# nrf52-coprocessor.net
KiCad netlist of a schematic drawn in Altium Designer
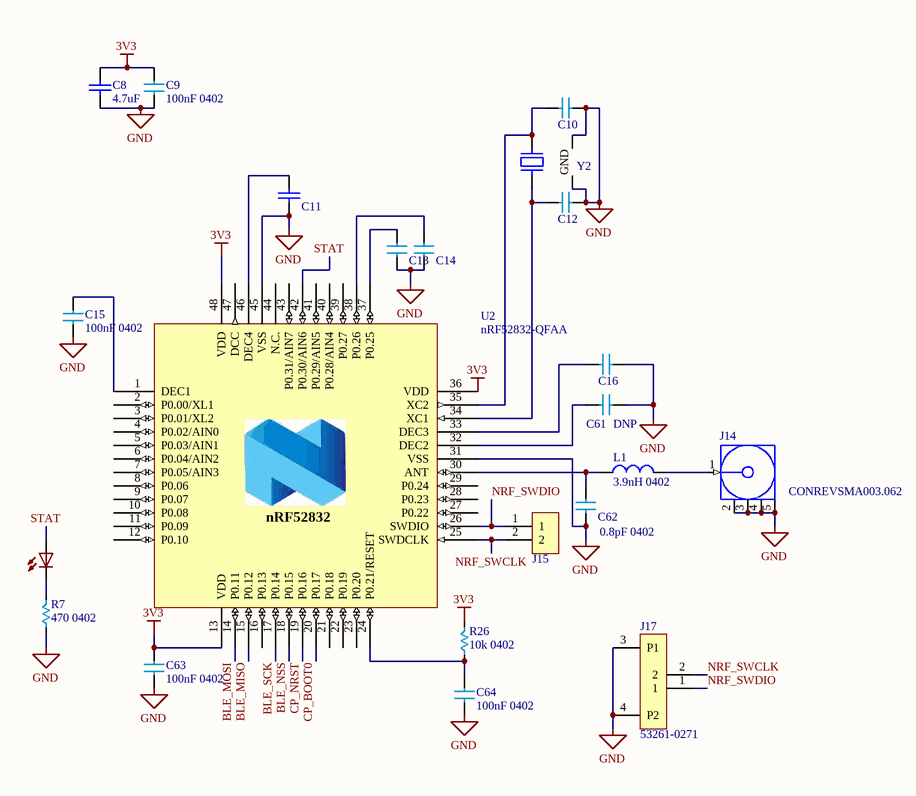
[diagram p0: nrf52-coprocessor.SchDoc]

(export (version "E")
  (design (tool "Eeschema 10.0.6"))
  (components
    (comp (ref "C8")
      (value "4.7uF")
      (footprint "C0603")
      (description "4.7uF 0603")
      (fields
        (field (name "MANUFACTURER") "Samsung")
        (field (name "MANUFACTURER PART NUMBER") "CL05F104ZO5NNNC")
        (field (name "PUBLISHER") "Altium Limited")
      )
      (libsource (lib "RLC") (part "C-4.7uF-0603"))
    )
    (comp (ref "C9") (value "100nF 0402") (footprint "C0402") (libsource (lib "RLC") (part "C0402-100nF")))
    (comp (ref "C10") (value "12pF 0402") (footprint "C0402") (libsource (lib "RLC") (part "C0402-12pF")))
    (comp (ref "C11")
      (value "1uF 0603")
      (footprint "C0603")
      (description "CAP CER 1UF 10V X7R 0603")
      (fields
        (field (name "MANUFACTURER") "Samsung")
        (field (name "MANUFACTURER PART NUMBER") "CL10B105KP8NFNC")
      )
      (libsource (lib "RLC") (part "C-1uF-0603"))
    )
    (comp (ref "C12") (value "12pF 0402") (footprint "C0402") (libsource (lib "RLC") (part "C0402-12pF")))
    (comp (ref "C13") (value "12pF 0402") (footprint "C0402") (libsource (lib "RLC") (part "C0402-12pF")))
    (comp (ref "C14") (value "12pF 0402") (footprint "C0402") (libsource (lib "RLC") (part "C0402-12pF")))
    (comp (ref "C15") (value "100nF 0402") (footprint "C0402") (libsource (lib "RLC") (part "C0402-100nF")))
    (comp (ref "C16") (value "100pF 0402") (footprint "C0402") (libsource (lib "RLC") (part "C0402-100pF")))
    (comp (ref "C61")
      (value "DNP")
      (footprint "C0402")
      (description "100pF 0402")
      (libsource (lib "RLC") (part "C0402-100pF"))
    )
    (comp (ref "C62") (value "0.8pF 0402") (footprint "C0402") (libsource (lib "RLC") (part "C0402-0.8pF")))
    (comp (ref "C63") (value "100nF 0402") (footprint "C0402") (libsource (lib "RLC") (part "C0402-100nF")))
    (comp (ref "C64") (value "100nF 0402") (footprint "C0402") (libsource (lib "RLC") (part "C0402-100nF")))
    (comp (ref "J14")
      (value "CONREVSMA003.062")
      (footprint "CON-SMA-EDGE062")
      (description "RP-SMA Female Edge Mount Connector for 0.062\" Thick Board")
      (libsource (lib "robot-cortex") (part "CONREVSMA003.062"))
    )
    (comp (ref "J15")
      (value "Header 2")
      (footprint "DUAL_PADS")
      (libsource (lib "robot-cortex") (part "DUAL_PADS"))
    )
    (comp (ref "J17")
      (value "53261-0271")
      (footprint "533980271")
      (description "Headers & Wire Housings 1.25MM HDR 2 CKT Right-Angle")
      (fields (field (name "MANUFACTURER") "Molex"))
      (libsource (lib "robot-cortex") (part "53261-0271"))
    )
    (comp (ref "L1")
      (value "3.9nH 0402")
      (footprint "L0402")
      (fields (field (name "MANUFACTURER") "Murata"))
      (libsource (lib "RLC") (part "L0402-3.9nH"))
    )
    (comp (ref "LED5")
      (value "LED WHITE 0603")
      (footprint "LED_0603")
      (description "LED   Source: http://www.osram.convergy.de   Source: www.luxeon.com   Source: www.kingbright.com")
      (fields
        (field (name "MANUFACTURER") "Dialight")
        (field (name "MANUFACTURER PART NUMBER") "5988070107F")
      )
      (libsource (lib "robot-cortex") (part "LED_ESML0603"))
    )
    (comp (ref "R7")
      (value "470 0402")
      (footprint "R0402")
      (fields
        (field (name "MANUFACTURER") "Yageo")
        (field (name "MANUFACTURER PART NUMBER") "RC0402JR-07470RL")
        (field (name "TOLERANCE") "5%")
      )
      (libsource (lib "robot-cortex") (part "R-470-0402"))
    )
    (comp (ref "R26") (value "10k 0402") (footprint "R0402") (libsource (lib "RLC") (part "R-10k-0402")))
    (comp (ref "U2")
      (value "nRF52832-QFAA")
      (footprint "QFN40P600X600X90-48N")
      (description "Multi-protocol Bluetooth Low Energy, ANT and 2.4GHz proprietary system-on-chip")
      (fields
        (field (name "MANUFACTURER") "Nordic Semiconductor")
        (field (name "PUBLISHER") "Nordic Semiconductor")
      )
      (libsource (lib "robot-cortex") (part "nRF52832_QFAA"))
    )
    (comp (ref "Y2")
      (value "32.0000 MHz 8pf")
      (footprint "robot-cortex:NDK NX3225GA")
      (description "CRYSTAL 32.0000MHZ 9PF SMD")
      (fields
        (field (name "MANUFACTURER") "NDK")
        (field (name "MANUFACTURER PART NUMBER") "NX3225SA-32MHZ-EXS00A-CS02368")
      )
      (libsource (lib "robot-cortex") (part "NX3225SA-32MHZ-EXS00A-CS02368"))
    )
  )
  (nets
    (net (code "1") (name "/BLE_MISO") (class "Default")
      (node (ref "U2") (pin "15") (pinfunction "P0.12_15") (pintype "bidirectional"))
    )
    (net (code "2") (name "/BLE_MOSI") (class "Default")
      (node (ref "U2") (pin "14") (pinfunction "P0.11_14") (pintype "bidirectional"))
    )
    (net (code "3") (name "/BLE_NSS") (class "Default")
      (node (ref "U2") (pin "18") (pinfunction "P0.15_18") (pintype "bidirectional"))
    )
    (net (code "4") (name "/BLE_SCK") (class "Default")
      (node (ref "U2") (pin "17") (pinfunction "P0.14_17") (pintype "bidirectional"))
    )
    (net (code "5") (name "/CP_BOOT0") (class "Default")
      (node (ref "U2") (pin "20") (pinfunction "P0.17_20") (pintype "bidirectional"))
    )
    (net (code "6") (name "/CP_NRST") (class "Default")
      (node (ref "U2") (pin "19") (pinfunction "P0.16_19") (pintype "bidirectional"))
    )
    (net (code "7") (name "/NRF_SWCLK") (class "Default")
      (node (ref "J15") (pin "2") (pinfunction "2_2") (pintype "power_in"))
      (node (ref "J17") (pin "2") (pinfunction "2_2") (pintype "power_in"))
      (node (ref "U2") (pin "25") (pinfunction "SWDCLK_25") (pintype "input"))
    )
    (net (code "8") (name "/NRF_SWDIO") (class "Default")
      (node (ref "J15") (pin "1") (pinfunction "1_1") (pintype "power_in"))
      (node (ref "J17") (pin "1") (pinfunction "1_1") (pintype "power_in"))
      (node (ref "U2") (pin "26") (pinfunction "SWDIO_26") (pintype "bidirectional"))
    )
    (net (code "9") (name "/STAT") (class "Default")
      (node (ref "LED5") (pin "A") (pinfunction "A_A") (pintype "passive"))
      (node (ref "U2") (pin "42") (pinfunction "P0.30/AIN6_42") (pintype "bidirectional"))
    )
    (net (code "10") (name "3V3") (class "Default")
      (node (ref "C63") (pin "2") (pinfunction "2_2") (pintype "passive"))
      (node (ref "C8") (pin "2") (pinfunction "2_2") (pintype "passive"))
      (node (ref "C9") (pin "2") (pinfunction "2_2") (pintype "passive"))
      (node (ref "R26") (pin "1") (pinfunction "1_1") (pintype "passive"))
      (node (ref "U2") (pin "13") (pinfunction "VDD_13") (pintype "power_in"))
      (node (ref "U2") (pin "36") (pinfunction "VDD_36") (pintype "power_in"))
      (node (ref "U2") (pin "48") (pinfunction "VDD_48") (pintype "power_in"))
    )
    (net (code "11") (name "GND") (class "Default")
      (node (ref "C10") (pin "2") (pinfunction "2_2") (pintype "passive"))
      (node (ref "C11") (pin "1") (pinfunction "1_1") (pintype "passive"))
      (node (ref "C12") (pin "2") (pinfunction "2_2") (pintype "passive"))
      (node (ref "C13") (pin "1") (pinfunction "1_1") (pintype "passive"))
      (node (ref "C14") (pin "1") (pinfunction "1_1") (pintype "passive"))
      (node (ref "C15") (pin "1") (pinfunction "1_1") (pintype "passive"))
      (node (ref "C16") (pin "2") (pinfunction "2_2") (pintype "passive"))
      (node (ref "C61") (pin "2") (pinfunction "2_2") (pintype "passive"))
      (node (ref "C62") (pin "2") (pinfunction "2_2") (pintype "passive"))
      (node (ref "C63") (pin "1") (pinfunction "1_1") (pintype "passive"))
      (node (ref "C64") (pin "2") (pinfunction "2_2") (pintype "passive"))
      (node (ref "C8") (pin "1") (pinfunction "1_1") (pintype "passive"))
      (node (ref "C9") (pin "1") (pinfunction "1_1") (pintype "passive"))
      (node (ref "J14") (pin "2") (pinfunction "GND_2") (pintype "power_in"))
      (node (ref "J14") (pin "3") (pinfunction "GND_3") (pintype "power_in"))
      (node (ref "J14") (pin "4") (pinfunction "GND_4") (pintype "power_in"))
      (node (ref "J14") (pin "5") (pinfunction "GND_5") (pintype "power_in"))
      (node (ref "J17") (pin "3") (pinfunction "P1_3") (pintype "power_in"))
      (node (ref "J17") (pin "4") (pinfunction "P2_4") (pintype "power_in"))
      (node (ref "R7") (pin "2") (pinfunction "2_2") (pintype "passive"))
      (node (ref "U2") (pin "31") (pinfunction "VSS_31") (pintype "power_in"))
      (node (ref "U2") (pin "45") (pinfunction "VSS_45") (pintype "power_in"))
      (node (ref "U2") (pin "49") (pinfunction "GND_49") (pintype "power_in"))
      (node (ref "Y2") (pin "2") (pinfunction "GND_2") (pintype "passive"))
      (node (ref "Y2") (pin "4") (pinfunction "GND_4") (pintype "passive"))
    )
    (net (code "12") (name "Net-(J14-Signal)") (class "Default")
      (node (ref "J14") (pin "1") (pinfunction "Signal_1") (pintype "input"))
      (node (ref "L1") (pin "2") (pinfunction "2_2") (pintype "passive"))
    )
    (net (code "13") (name "Net-(LED5-PadC)") (class "Default")
      (node (ref "LED5") (pin "C") (pinfunction "C_C") (pintype "passive"))
      (node (ref "R7") (pin "1") (pinfunction "1_1") (pintype "passive"))
    )
    (net (code "14") (name "Net-(U2-ANT)") (class "Default")
      (node (ref "C62") (pin "1") (pinfunction "1_1") (pintype "passive"))
      (node (ref "L1") (pin "1") (pinfunction "1_1") (pintype "passive"))
      (node (ref "U2") (pin "30") (pinfunction "ANT_30") (pintype "bidirectional"))
    )
    (net (code "15") (name "Net-(U2-DEC1)") (class "Default")
      (node (ref "C15") (pin "2") (pinfunction "2_2") (pintype "passive"))
      (node (ref "U2") (pin "1") (pinfunction "DEC1_1") (pintype "power_in"))
    )
    (net (code "16") (name "Net-(U2-DEC2)") (class "Default")
      (node (ref "C61") (pin "1") (pinfunction "1_1") (pintype "passive"))
      (node (ref "U2") (pin "32") (pinfunction "DEC2_32") (pintype "power_in"))
    )
    (net (code "17") (name "Net-(U2-DEC3)") (class "Default")
      (node (ref "C16") (pin "1") (pinfunction "1_1") (pintype "passive"))
      (node (ref "U2") (pin "33") (pinfunction "DEC3_33") (pintype "power_in"))
    )
    (net (code "18") (name "Net-(U2-DEC4)") (class "Default")
      (node (ref "C11") (pin "2") (pinfunction "2_2") (pintype "passive"))
      (node (ref "U2") (pin "46") (pinfunction "DEC4_46") (pintype "power_in"))
    )
    (net (code "19") (name "Net-(U2-P0.21{slash}RESET)") (class "Default")
      (node (ref "C64") (pin "1") (pinfunction "1_1") (pintype "passive"))
      (node (ref "R26") (pin "2") (pinfunction "2_2") (pintype "passive"))
      (node (ref "U2") (pin "24") (pinfunction "P0.21/RESET_24") (pintype "bidirectional"))
    )
    (net (code "20") (name "Net-(U2-P0.25)") (class "Default")
      (node (ref "C13") (pin "2") (pinfunction "2_2") (pintype "passive"))
      (node (ref "U2") (pin "37") (pinfunction "P0.25_37") (pintype "bidirectional"))
    )
    (net (code "21") (name "Net-(U2-P0.26)") (class "Default")
      (node (ref "C14") (pin "2") (pinfunction "2_2") (pintype "passive"))
      (node (ref "U2") (pin "38") (pinfunction "P0.26_38") (pintype "bidirectional"))
    )
    (net (code "22") (name "Net-(U2-XC1)") (class "Default")
      (node (ref "C12") (pin "1") (pinfunction "1_1") (pintype "passive"))
      (node (ref "U2") (pin "34") (pinfunction "XC1_34") (pintype "input"))
      (node (ref "Y2") (pin "1") (pinfunction "1_1") (pintype "passive"))
    )
    (net (code "23") (name "Net-(U2-XC2)") (class "Default")
      (node (ref "C10") (pin "1") (pinfunction "1_1") (pintype "passive"))
      (node (ref "U2") (pin "35") (pinfunction "XC2_35") (pintype "output"))
      (node (ref "Y2") (pin "3") (pinfunction "3_3") (pintype "passive"))
    )
    (net (code "24") (name "unconnected-(U2-DCC-Pad47)") (class "Default")
      (node (ref "U2") (pin "47") (pinfunction "DCC_47") (pintype "output"))
    )
    (net (code "25") (name "unconnected-(U2-N.C.-Pad44)") (class "Default")
      (node (ref "U2") (pin "44") (pinfunction "N.C._44") (pintype "power_in"))
    )
    (net (code "26") (name "unconnected-(U2-P0.00{slash}XL1-Pad2)") (class "Default")
      (node (ref "U2") (pin "2") (pinfunction "P0.00/XL1_2") (pintype "bidirectional"))
    )
    (net (code "27") (name "unconnected-(U2-P0.01{slash}XL2-Pad3)") (class "Default")
      (node (ref "U2") (pin "3") (pinfunction "P0.01/XL2_3") (pintype "bidirectional"))
    )
    (net (code "28") (name "unconnected-(U2-P0.02{slash}AIN0-Pad4)") (class "Default")
      (node (ref "U2") (pin "4") (pinfunction "P0.02/AIN0_4") (pintype "bidirectional"))
    )
    (net (code "29") (name "unconnected-(U2-P0.03{slash}AIN1-Pad5)") (class "Default")
      (node (ref "U2") (pin "5") (pinfunction "P0.03/AIN1_5") (pintype "bidirectional"))
    )
    (net (code "30") (name "unconnected-(U2-P0.04{slash}AIN2-Pad6)") (class "Default")
      (node (ref "U2") (pin "6") (pinfunction "P0.04/AIN2_6") (pintype "bidirectional"))
    )
    (net (code "31") (name "unconnected-(U2-P0.05{slash}AIN3-Pad7)") (class "Default")
      (node (ref "U2") (pin "7") (pinfunction "P0.05/AIN3_7") (pintype "bidirectional"))
    )
    (net (code "32") (name "unconnected-(U2-P0.06-Pad8)") (class "Default")
      (node (ref "U2") (pin "8") (pinfunction "P0.06_8") (pintype "bidirectional"))
    )
    (net (code "33") (name "unconnected-(U2-P0.07-Pad9)") (class "Default")
      (node (ref "U2") (pin "9") (pinfunction "P0.07_9") (pintype "bidirectional"))
    )
    (net (code "34") (name "unconnected-(U2-P0.08-Pad10)") (class "Default")
      (node (ref "U2") (pin "10") (pinfunction "P0.08_10") (pintype "bidirectional"))
    )
    (net (code "35") (name "unconnected-(U2-P0.09-Pad11)") (class "Default")
      (node (ref "U2") (pin "11") (pinfunction "P0.09_11") (pintype "bidirectional"))
    )
    (net (code "36") (name "unconnected-(U2-P0.10-Pad12)") (class "Default")
      (node (ref "U2") (pin "12") (pinfunction "P0.10_12") (pintype "bidirectional"))
    )
    (net (code "37") (name "unconnected-(U2-P0.13-Pad16)") (class "Default")
      (node (ref "U2") (pin "16") (pinfunction "P0.13_16") (pintype "bidirectional"))
    )
    (net (code "38") (name "unconnected-(U2-P0.18-Pad21)") (class "Default")
      (node (ref "U2") (pin "21") (pinfunction "P0.18_21") (pintype "bidirectional"))
    )
    (net (code "39") (name "unconnected-(U2-P0.19-Pad22)") (class "Default")
      (node (ref "U2") (pin "22") (pinfunction "P0.19_22") (pintype "bidirectional"))
    )
    (net (code "40") (name "unconnected-(U2-P0.20-Pad23)") (class "Default")
      (node (ref "U2") (pin "23") (pinfunction "P0.20_23") (pintype "bidirectional"))
    )
    (net (code "41") (name "unconnected-(U2-P0.22-Pad27)") (class "Default")
      (node (ref "U2") (pin "27") (pinfunction "P0.22_27") (pintype "bidirectional"))
    )
    (net (code "42") (name "unconnected-(U2-P0.23-Pad28)") (class "Default")
      (node (ref "U2") (pin "28") (pinfunction "P0.23_28") (pintype "bidirectional"))
    )
    (net (code "43") (name "unconnected-(U2-P0.24-Pad29)") (class "Default")
      (node (ref "U2") (pin "29") (pinfunction "P0.24_29") (pintype "bidirectional"))
    )
    (net (code "44") (name "unconnected-(U2-P0.27-Pad39)") (class "Default")
      (node (ref "U2") (pin "39") (pinfunction "P0.27_39") (pintype "bidirectional"))
    )
    (net (code "45") (name "unconnected-(U2-P0.28{slash}AIN4-Pad40)") (class "Default")
      (node (ref "U2") (pin "40") (pinfunction "P0.28/AIN4_40") (pintype "bidirectional"))
    )
    (net (code "46") (name "unconnected-(U2-P0.29{slash}AIN5-Pad41)") (class "Default")
      (node (ref "U2") (pin "41") (pinfunction "P0.29/AIN5_41") (pintype "bidirectional"))
    )
    (net (code "47") (name "unconnected-(U2-P0.31{slash}AIN7-Pad43)") (class "Default")
      (node (ref "U2") (pin "43") (pinfunction "P0.31/AIN7_43") (pintype "bidirectional"))
    )
  )
)
